# driver2.net
KiCad netlist of a schematic drawn in EAGLE
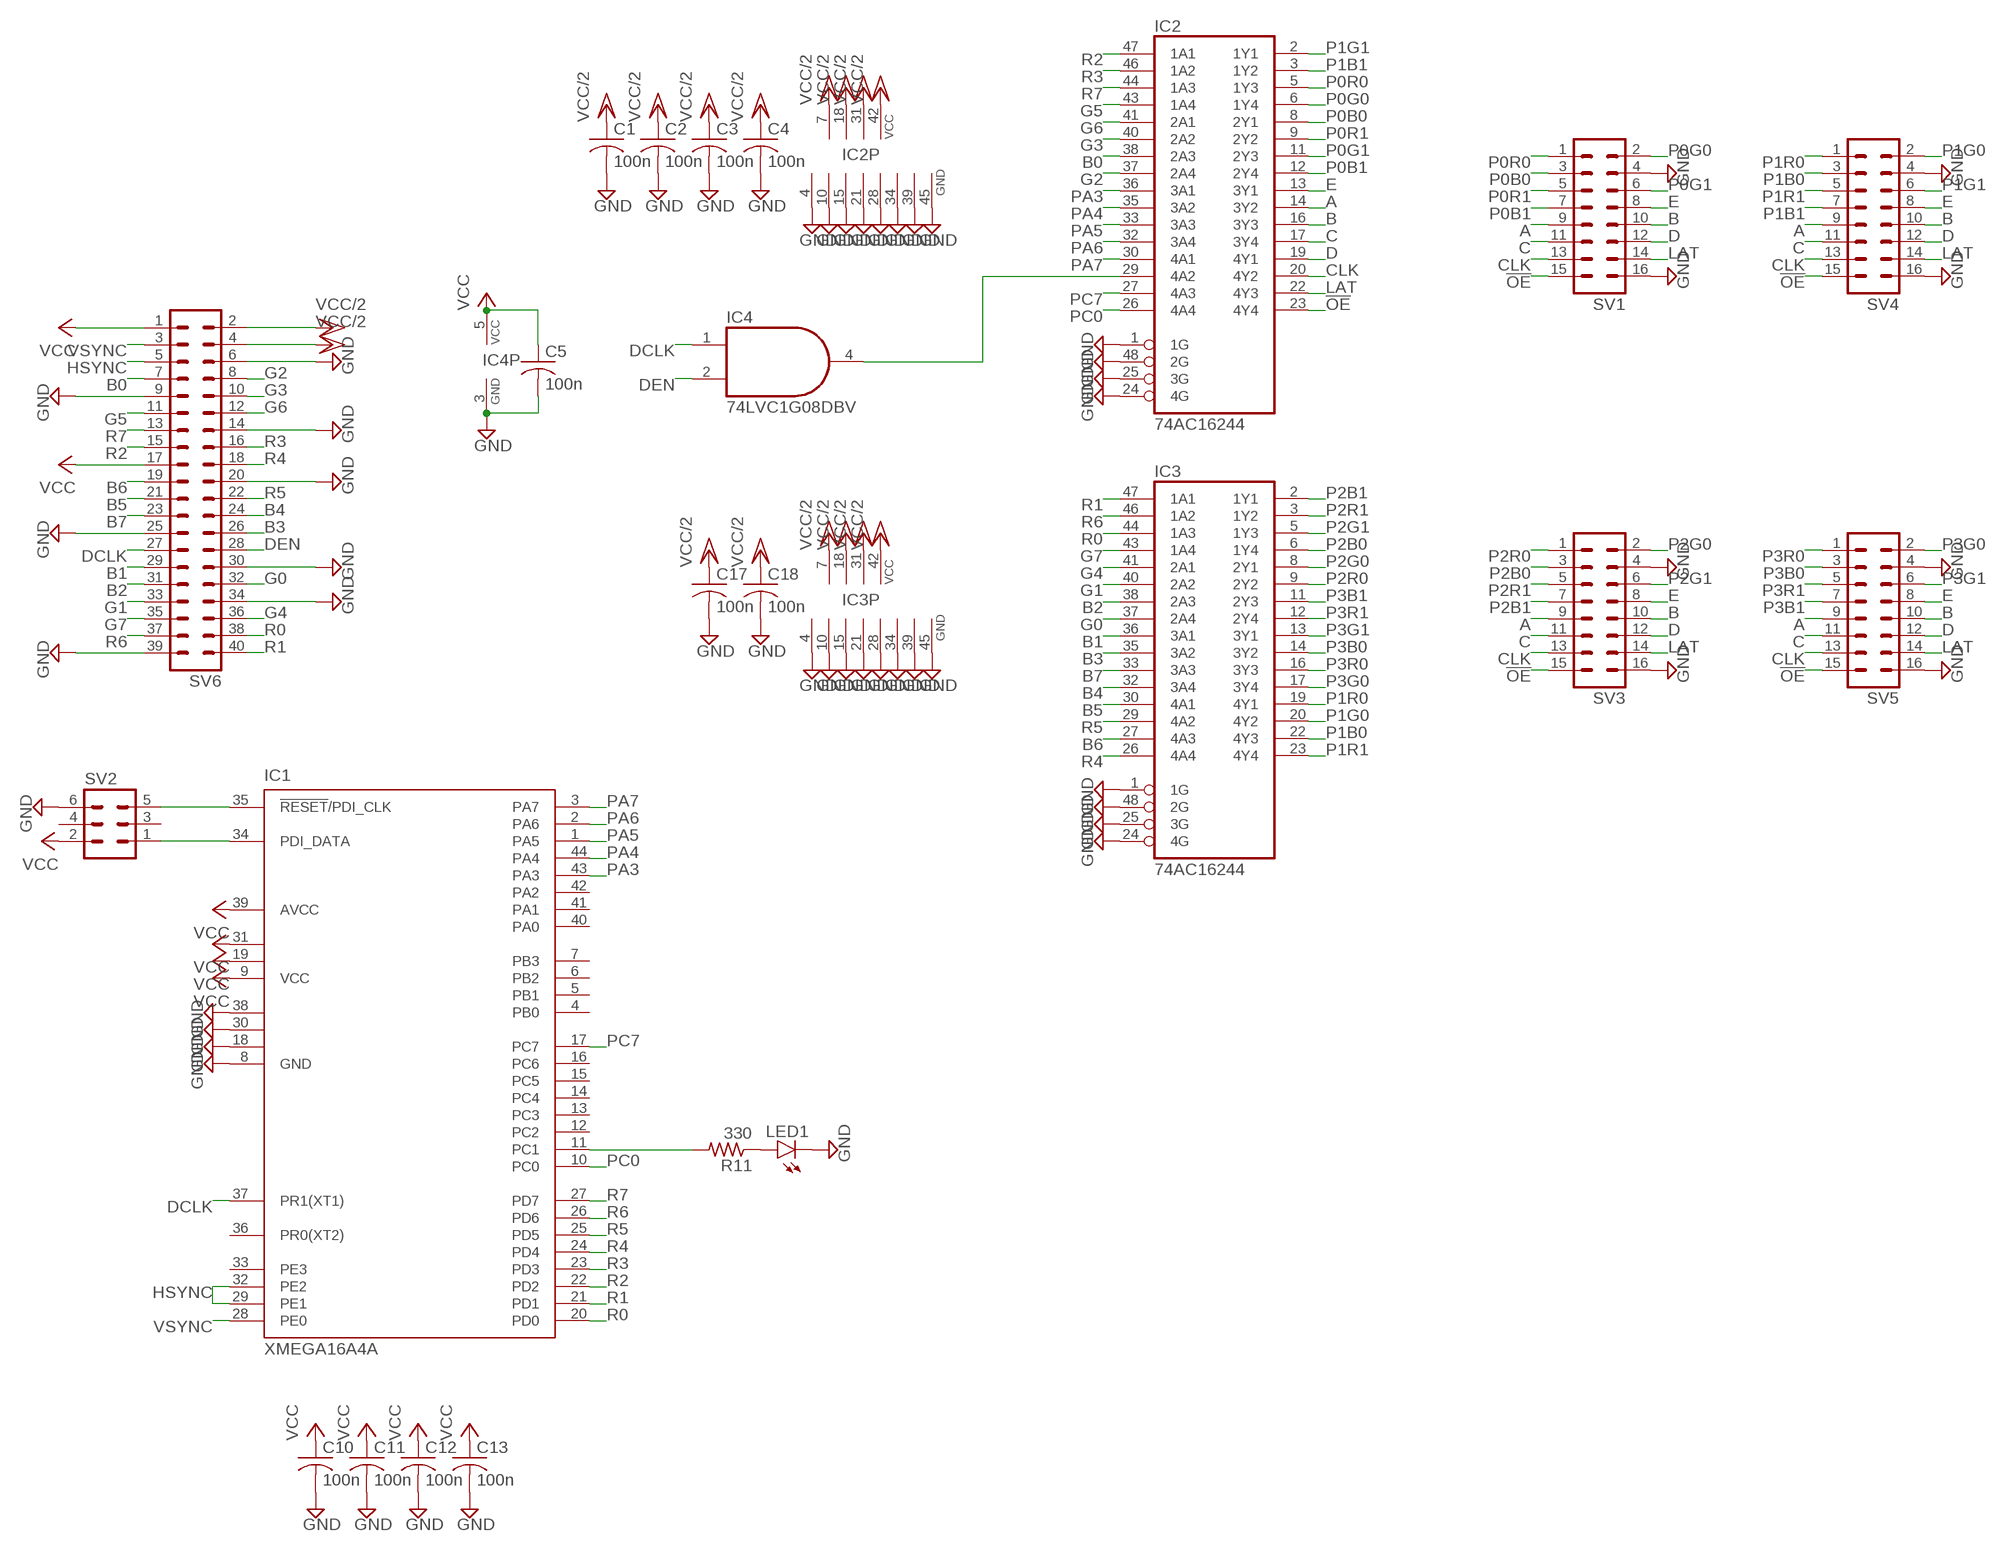
[diagram p0: schematic, sheet 1]

(export (version "E")
  (design (tool "Eeschema 10.0.6"))
  (components
    (comp (ref "C1")
      (value "100n")
      (footprint "eagle-import:C0402")
      (libsource (lib "eagle-import") (part "C-USC0402"))
    )
    (comp (ref "C2")
      (value "100n")
      (footprint "eagle-import:C0402")
      (libsource (lib "eagle-import") (part "C-USC0402"))
    )
    (comp (ref "C3")
      (value "100n")
      (footprint "eagle-import:C0402")
      (libsource (lib "eagle-import") (part "C-USC0402"))
    )
    (comp (ref "C4")
      (value "100n")
      (footprint "eagle-import:C0402")
      (libsource (lib "eagle-import") (part "C-USC0402"))
    )
    (comp (ref "C5")
      (value "100n")
      (footprint "eagle-import:C0402")
      (libsource (lib "eagle-import") (part "C-USC0402"))
    )
    (comp (ref "C10")
      (value "100n")
      (footprint "eagle-import:C0402")
      (libsource (lib "eagle-import") (part "C-USC0402"))
    )
    (comp (ref "C11")
      (value "100n")
      (footprint "eagle-import:C0402")
      (libsource (lib "eagle-import") (part "C-USC0402"))
    )
    (comp (ref "C12")
      (value "100n")
      (footprint "eagle-import:C0402")
      (libsource (lib "eagle-import") (part "C-USC0402"))
    )
    (comp (ref "C13")
      (value "100n")
      (footprint "eagle-import:C0402")
      (libsource (lib "eagle-import") (part "C-USC0402"))
    )
    (comp (ref "C17")
      (value "100n")
      (footprint "eagle-import:C0402")
      (libsource (lib "eagle-import") (part "C-USC0402"))
    )
    (comp (ref "C18")
      (value "100n")
      (footprint "eagle-import:C0402")
      (libsource (lib "eagle-import") (part "C-USC0402"))
    )
    (comp (ref "IC1")
      (value "XMEGA16A4A")
      (footprint "eagle-import:TQFP44")
      (libsource (lib "eagle-import") (part "XMEGA16A4A"))
    )
    (comp (ref "IC2")
      (value "74AC16244")
      (footprint "eagle-import:SSOP48DL")
      (libsource (lib "eagle-import") (part "74AC16244"))
    )
    (comp (ref "IC3")
      (value "74AC16244")
      (footprint "eagle-import:SSOP48DL")
      (libsource (lib "eagle-import") (part "74AC16244"))
    )
    (comp (ref "IC4")
      (value "74LVC1G08DBV")
      (footprint "eagle-import:SOT23-5")
      (libsource (lib "eagle-import") (part "741G08DBVLVC"))
    )
    (comp (ref "LED1")
      (value "LEDCHIPLED_0805")
      (footprint "eagle-import:CHIPLED_0805")
      (libsource (lib "eagle-import") (part "LEDCHIPLED_0805"))
    )
    (comp (ref "R11")
      (value "330")
      (footprint "eagle-import:R0402")
      (libsource (lib "eagle-import") (part "R-US_R0402"))
    )
    (comp (ref "SV1")
      (value "MA08-2")
      (footprint "eagle-import:MA08-2")
      (libsource (lib "eagle-import") (part "MA08-2"))
    )
    (comp (ref "SV2")
      (value "MA03-2")
      (footprint "eagle-import:MA03-2")
      (libsource (lib "eagle-import") (part "MA03-2"))
    )
    (comp (ref "SV3")
      (value "MA08-2")
      (footprint "eagle-import:MA08-2")
      (libsource (lib "eagle-import") (part "MA08-2"))
    )
    (comp (ref "SV4")
      (value "MA08-2")
      (footprint "eagle-import:MA08-2")
      (libsource (lib "eagle-import") (part "MA08-2"))
    )
    (comp (ref "SV5")
      (value "MA08-2")
      (footprint "eagle-import:MA08-2")
      (libsource (lib "eagle-import") (part "MA08-2"))
    )
    (comp (ref "SV6")
      (value "MA20-2")
      (footprint "eagle-import:MA20-2")
      (libsource (lib "eagle-import") (part "MA20-2"))
    )
  )
  (nets
    (net (code "1") (name "/A") (class "Default")
      (node (ref "IC2") (pin "14") (pinfunction "3Y2_14") (pintype "tri_state"))
      (node (ref "SV1") (pin "9") (pinfunction "9_9") (pintype "passive"))
      (node (ref "SV3") (pin "9") (pinfunction "9_9") (pintype "passive"))
      (node (ref "SV4") (pin "9") (pinfunction "9_9") (pintype "passive"))
      (node (ref "SV5") (pin "9") (pinfunction "9_9") (pintype "passive"))
    )
    (net (code "2") (name "/B") (class "Default")
      (node (ref "IC2") (pin "16") (pinfunction "3Y3_16") (pintype "tri_state"))
      (node (ref "SV1") (pin "10") (pinfunction "10_10") (pintype "passive"))
      (node (ref "SV3") (pin "10") (pinfunction "10_10") (pintype "passive"))
      (node (ref "SV4") (pin "10") (pinfunction "10_10") (pintype "passive"))
      (node (ref "SV5") (pin "10") (pinfunction "10_10") (pintype "passive"))
    )
    (net (code "3") (name "/B0") (class "Default")
      (node (ref "IC2") (pin "38") (pinfunction "2A3_38") (pintype "input"))
      (node (ref "SV6") (pin "7") (pinfunction "7_7") (pintype "passive"))
    )
    (net (code "4") (name "/B1") (class "Default")
      (node (ref "IC3") (pin "36") (pinfunction "3A1_36") (pintype "input"))
      (node (ref "SV6") (pin "29") (pinfunction "29_29") (pintype "passive"))
    )
    (net (code "5") (name "/B2") (class "Default")
      (node (ref "IC3") (pin "38") (pinfunction "2A3_38") (pintype "input"))
      (node (ref "SV6") (pin "31") (pinfunction "31_31") (pintype "passive"))
    )
    (net (code "6") (name "/B3") (class "Default")
      (node (ref "IC3") (pin "35") (pinfunction "3A2_35") (pintype "input"))
      (node (ref "SV6") (pin "26") (pinfunction "26_26") (pintype "passive"))
    )
    (net (code "7") (name "/B4") (class "Default")
      (node (ref "IC3") (pin "32") (pinfunction "3A4_32") (pintype "input"))
      (node (ref "SV6") (pin "24") (pinfunction "24_24") (pintype "passive"))
    )
    (net (code "8") (name "/B5") (class "Default")
      (node (ref "IC3") (pin "30") (pinfunction "4A1_30") (pintype "input"))
      (node (ref "SV6") (pin "21") (pinfunction "21_21") (pintype "passive"))
    )
    (net (code "9") (name "/B6") (class "Default")
      (node (ref "IC3") (pin "27") (pinfunction "4A3_27") (pintype "input"))
      (node (ref "SV6") (pin "19") (pinfunction "19_19") (pintype "passive"))
    )
    (net (code "10") (name "/B7") (class "Default")
      (node (ref "IC3") (pin "33") (pinfunction "3A3_33") (pintype "input"))
      (node (ref "SV6") (pin "23") (pinfunction "23_23") (pintype "passive"))
    )
    (net (code "11") (name "/C") (class "Default")
      (node (ref "IC2") (pin "17") (pinfunction "3Y4_17") (pintype "tri_state"))
      (node (ref "SV1") (pin "11") (pinfunction "11_11") (pintype "passive"))
      (node (ref "SV3") (pin "11") (pinfunction "11_11") (pintype "passive"))
      (node (ref "SV4") (pin "11") (pinfunction "11_11") (pintype "passive"))
      (node (ref "SV5") (pin "11") (pinfunction "11_11") (pintype "passive"))
    )
    (net (code "12") (name "/CLK") (class "Default")
      (node (ref "IC2") (pin "20") (pinfunction "4Y2_20") (pintype "tri_state"))
      (node (ref "SV1") (pin "13") (pinfunction "13_13") (pintype "passive"))
      (node (ref "SV3") (pin "13") (pinfunction "13_13") (pintype "passive"))
      (node (ref "SV4") (pin "13") (pinfunction "13_13") (pintype "passive"))
      (node (ref "SV5") (pin "13") (pinfunction "13_13") (pintype "passive"))
    )
    (net (code "13") (name "/D") (class "Default")
      (node (ref "IC2") (pin "19") (pinfunction "4Y1_19") (pintype "tri_state"))
      (node (ref "SV1") (pin "12") (pinfunction "12_12") (pintype "passive"))
      (node (ref "SV3") (pin "12") (pinfunction "12_12") (pintype "passive"))
      (node (ref "SV4") (pin "12") (pinfunction "12_12") (pintype "passive"))
      (node (ref "SV5") (pin "12") (pinfunction "12_12") (pintype "passive"))
    )
    (net (code "14") (name "/DCLK") (class "Default")
      (node (ref "IC1") (pin "37") (pinfunction "PR1(XT1)_37") (pintype "bidirectional"))
      (node (ref "IC4") (pin "1") (pinfunction "I0_1") (pintype "input"))
      (node (ref "SV6") (pin "27") (pinfunction "27_27") (pintype "passive"))
    )
    (net (code "15") (name "/DEN") (class "Default")
      (node (ref "IC4") (pin "2") (pinfunction "I1_2") (pintype "input"))
      (node (ref "SV6") (pin "28") (pinfunction "28_28") (pintype "passive"))
    )
    (net (code "16") (name "/E") (class "Default")
      (node (ref "IC2") (pin "13") (pinfunction "3Y1_13") (pintype "tri_state"))
      (node (ref "SV1") (pin "8") (pinfunction "8_8") (pintype "passive"))
      (node (ref "SV3") (pin "8") (pinfunction "8_8") (pintype "passive"))
      (node (ref "SV4") (pin "8") (pinfunction "8_8") (pintype "passive"))
      (node (ref "SV5") (pin "8") (pinfunction "8_8") (pintype "passive"))
    )
    (net (code "17") (name "/G0") (class "Default")
      (node (ref "IC3") (pin "37") (pinfunction "2A4_37") (pintype "input"))
      (node (ref "SV6") (pin "32") (pinfunction "32_32") (pintype "passive"))
    )
    (net (code "18") (name "/G1") (class "Default")
      (node (ref "IC3") (pin "40") (pinfunction "2A2_40") (pintype "input"))
      (node (ref "SV6") (pin "33") (pinfunction "33_33") (pintype "passive"))
    )
    (net (code "19") (name "/G2") (class "Default")
      (node (ref "IC2") (pin "37") (pinfunction "2A4_37") (pintype "input"))
      (node (ref "SV6") (pin "8") (pinfunction "8_8") (pintype "passive"))
    )
    (net (code "20") (name "/G3") (class "Default")
      (node (ref "IC2") (pin "40") (pinfunction "2A2_40") (pintype "input"))
      (node (ref "SV6") (pin "10") (pinfunction "10_10") (pintype "passive"))
    )
    (net (code "21") (name "/G4") (class "Default")
      (node (ref "IC3") (pin "41") (pinfunction "2A1_41") (pintype "input"))
      (node (ref "SV6") (pin "36") (pinfunction "36_36") (pintype "passive"))
    )
    (net (code "22") (name "/G5") (class "Default")
      (node (ref "IC2") (pin "43") (pinfunction "1A4_43") (pintype "input"))
      (node (ref "SV6") (pin "11") (pinfunction "11_11") (pintype "passive"))
    )
    (net (code "23") (name "/G6") (class "Default")
      (node (ref "IC2") (pin "41") (pinfunction "2A1_41") (pintype "input"))
      (node (ref "SV6") (pin "12") (pinfunction "12_12") (pintype "passive"))
    )
    (net (code "24") (name "/G7") (class "Default")
      (node (ref "IC3") (pin "43") (pinfunction "1A4_43") (pintype "input"))
      (node (ref "SV6") (pin "35") (pinfunction "35_35") (pintype "passive"))
    )
    (net (code "25") (name "/HSYNC") (class "Default")
      (node (ref "IC1") (pin "29") (pinfunction "PE1_29") (pintype "bidirectional"))
      (node (ref "IC1") (pin "32") (pinfunction "PE2_32") (pintype "bidirectional"))
      (node (ref "SV6") (pin "5") (pinfunction "5_5") (pintype "passive"))
    )
    (net (code "26") (name "/LAT") (class "Default")
      (node (ref "IC2") (pin "22") (pinfunction "4Y3_22") (pintype "tri_state"))
      (node (ref "SV1") (pin "14") (pinfunction "14_14") (pintype "passive"))
      (node (ref "SV3") (pin "14") (pinfunction "14_14") (pintype "passive"))
      (node (ref "SV4") (pin "14") (pinfunction "14_14") (pintype "passive"))
      (node (ref "SV5") (pin "14") (pinfunction "14_14") (pintype "passive"))
    )
    (net (code "27") (name "/P0B0") (class "Default")
      (node (ref "IC2") (pin "8") (pinfunction "2Y1_8") (pintype "tri_state"))
      (node (ref "SV1") (pin "3") (pinfunction "3_3") (pintype "passive"))
    )
    (net (code "28") (name "/P0B1") (class "Default")
      (node (ref "IC2") (pin "12") (pinfunction "2Y4_12") (pintype "tri_state"))
      (node (ref "SV1") (pin "7") (pinfunction "7_7") (pintype "passive"))
    )
    (net (code "29") (name "/P0G0") (class "Default")
      (node (ref "IC2") (pin "6") (pinfunction "1Y4_6") (pintype "tri_state"))
      (node (ref "SV1") (pin "2") (pinfunction "2_2") (pintype "passive"))
    )
    (net (code "30") (name "/P0G1") (class "Default")
      (node (ref "IC2") (pin "11") (pinfunction "2Y3_11") (pintype "tri_state"))
      (node (ref "SV1") (pin "6") (pinfunction "6_6") (pintype "passive"))
    )
    (net (code "31") (name "/P0R0") (class "Default")
      (node (ref "IC2") (pin "5") (pinfunction "1Y3_5") (pintype "tri_state"))
      (node (ref "SV1") (pin "1") (pinfunction "1_1") (pintype "passive"))
    )
    (net (code "32") (name "/P0R1") (class "Default")
      (node (ref "IC2") (pin "9") (pinfunction "2Y2_9") (pintype "tri_state"))
      (node (ref "SV1") (pin "5") (pinfunction "5_5") (pintype "passive"))
    )
    (net (code "33") (name "/P1B0") (class "Default")
      (node (ref "IC3") (pin "22") (pinfunction "4Y3_22") (pintype "tri_state"))
      (node (ref "SV4") (pin "3") (pinfunction "3_3") (pintype "passive"))
    )
    (net (code "34") (name "/P1B1") (class "Default")
      (node (ref "IC2") (pin "3") (pinfunction "1Y2_3") (pintype "tri_state"))
      (node (ref "SV4") (pin "7") (pinfunction "7_7") (pintype "passive"))
    )
    (net (code "35") (name "/P1G0") (class "Default")
      (node (ref "IC3") (pin "20") (pinfunction "4Y2_20") (pintype "tri_state"))
      (node (ref "SV4") (pin "2") (pinfunction "2_2") (pintype "passive"))
    )
    (net (code "36") (name "/P1G1") (class "Default")
      (node (ref "IC2") (pin "2") (pinfunction "1Y1_2") (pintype "tri_state"))
      (node (ref "SV4") (pin "6") (pinfunction "6_6") (pintype "passive"))
    )
    (net (code "37") (name "/P1R0") (class "Default")
      (node (ref "IC3") (pin "19") (pinfunction "4Y1_19") (pintype "tri_state"))
      (node (ref "SV4") (pin "1") (pinfunction "1_1") (pintype "passive"))
    )
    (net (code "38") (name "/P1R1") (class "Default")
      (node (ref "IC3") (pin "23") (pinfunction "4Y4_23") (pintype "tri_state"))
      (node (ref "SV4") (pin "5") (pinfunction "5_5") (pintype "passive"))
    )
    (net (code "39") (name "/P2B0") (class "Default")
      (node (ref "IC3") (pin "6") (pinfunction "1Y4_6") (pintype "tri_state"))
      (node (ref "SV3") (pin "3") (pinfunction "3_3") (pintype "passive"))
    )
    (net (code "40") (name "/P2B1") (class "Default")
      (node (ref "IC3") (pin "2") (pinfunction "1Y1_2") (pintype "tri_state"))
      (node (ref "SV3") (pin "7") (pinfunction "7_7") (pintype "passive"))
    )
    (net (code "41") (name "/P2G0") (class "Default")
      (node (ref "IC3") (pin "8") (pinfunction "2Y1_8") (pintype "tri_state"))
      (node (ref "SV3") (pin "2") (pinfunction "2_2") (pintype "passive"))
    )
    (net (code "42") (name "/P2G1") (class "Default")
      (node (ref "IC3") (pin "5") (pinfunction "1Y3_5") (pintype "tri_state"))
      (node (ref "SV3") (pin "6") (pinfunction "6_6") (pintype "passive"))
    )
    (net (code "43") (name "/P2R0") (class "Default")
      (node (ref "IC3") (pin "9") (pinfunction "2Y2_9") (pintype "tri_state"))
      (node (ref "SV3") (pin "1") (pinfunction "1_1") (pintype "passive"))
    )
    (net (code "44") (name "/P2R1") (class "Default")
      (node (ref "IC3") (pin "3") (pinfunction "1Y2_3") (pintype "tri_state"))
      (node (ref "SV3") (pin "5") (pinfunction "5_5") (pintype "passive"))
    )
    (net (code "45") (name "/P3B0") (class "Default")
      (node (ref "IC3") (pin "14") (pinfunction "3Y2_14") (pintype "tri_state"))
      (node (ref "SV5") (pin "3") (pinfunction "3_3") (pintype "passive"))
    )
    (net (code "46") (name "/P3B1") (class "Default")
      (node (ref "IC3") (pin "11") (pinfunction "2Y3_11") (pintype "tri_state"))
      (node (ref "SV5") (pin "7") (pinfunction "7_7") (pintype "passive"))
    )
    (net (code "47") (name "/P3G0") (class "Default")
      (node (ref "IC3") (pin "17") (pinfunction "3Y4_17") (pintype "tri_state"))
      (node (ref "SV5") (pin "2") (pinfunction "2_2") (pintype "passive"))
    )
    (net (code "48") (name "/P3G1") (class "Default")
      (node (ref "IC3") (pin "13") (pinfunction "3Y1_13") (pintype "tri_state"))
      (node (ref "SV5") (pin "6") (pinfunction "6_6") (pintype "passive"))
    )
    (net (code "49") (name "/P3R0") (class "Default")
      (node (ref "IC3") (pin "16") (pinfunction "3Y3_16") (pintype "tri_state"))
      (node (ref "SV5") (pin "1") (pinfunction "1_1") (pintype "passive"))
    )
    (net (code "50") (name "/P3R1") (class "Default")
      (node (ref "IC3") (pin "12") (pinfunction "2Y4_12") (pintype "tri_state"))
      (node (ref "SV5") (pin "5") (pinfunction "5_5") (pintype "passive"))
    )
    (net (code "51") (name "/PA3") (class "Default")
      (node (ref "IC1") (pin "43") (pinfunction "PA3_43") (pintype "bidirectional"))
      (node (ref "IC2") (pin "36") (pinfunction "3A1_36") (pintype "input"))
    )
    (net (code "52") (name "/PA4") (class "Default")
      (node (ref "IC1") (pin "44") (pinfunction "PA4_44") (pintype "bidirectional"))
      (node (ref "IC2") (pin "35") (pinfunction "3A2_35") (pintype "input"))
    )
    (net (code "53") (name "/PA5") (class "Default")
      (node (ref "IC1") (pin "1") (pinfunction "PA5_1") (pintype "bidirectional"))
      (node (ref "IC2") (pin "33") (pinfunction "3A3_33") (pintype "input"))
    )
    (net (code "54") (name "/PA6") (class "Default")
      (node (ref "IC1") (pin "2") (pinfunction "PA6_2") (pintype "bidirectional"))
      (node (ref "IC2") (pin "32") (pinfunction "3A4_32") (pintype "input"))
    )
    (net (code "55") (name "/PA7") (class "Default")
      (node (ref "IC1") (pin "3") (pinfunction "PA7_3") (pintype "bidirectional"))
      (node (ref "IC2") (pin "30") (pinfunction "4A1_30") (pintype "input"))
    )
    (net (code "56") (name "/PC0") (class "Default")
      (node (ref "IC1") (pin "10") (pinfunction "PC0_10") (pintype "bidirectional"))
      (node (ref "IC2") (pin "26") (pinfunction "4A4_26") (pintype "input"))
    )
    (net (code "57") (name "/PC7") (class "Default")
      (node (ref "IC1") (pin "17") (pinfunction "PC7_17") (pintype "bidirectional"))
      (node (ref "IC2") (pin "27") (pinfunction "4A3_27") (pintype "input"))
    )
    (net (code "58") (name "/R0") (class "Default")
      (node (ref "IC1") (pin "20") (pinfunction "PD0_20") (pintype "bidirectional"))
      (node (ref "IC3") (pin "44") (pinfunction "1A3_44") (pintype "input"))
      (node (ref "SV6") (pin "38") (pinfunction "38_38") (pintype "passive"))
    )
    (net (code "59") (name "/R1") (class "Default")
      (node (ref "IC1") (pin "21") (pinfunction "PD1_21") (pintype "bidirectional"))
      (node (ref "IC3") (pin "47") (pinfunction "1A1_47") (pintype "input"))
      (node (ref "SV6") (pin "40") (pinfunction "40_40") (pintype "passive"))
    )
    (net (code "60") (name "/R2") (class "Default")
      (node (ref "IC1") (pin "22") (pinfunction "PD2_22") (pintype "bidirectional"))
      (node (ref "IC2") (pin "47") (pinfunction "1A1_47") (pintype "input"))
      (node (ref "SV6") (pin "15") (pinfunction "15_15") (pintype "passive"))
    )
    (net (code "61") (name "/R3") (class "Default")
      (node (ref "IC1") (pin "23") (pinfunction "PD3_23") (pintype "bidirectional"))
      (node (ref "IC2") (pin "46") (pinfunction "1A2_46") (pintype "input"))
      (node (ref "SV6") (pin "16") (pinfunction "16_16") (pintype "passive"))
    )
    (net (code "62") (name "/R4") (class "Default")
      (node (ref "IC1") (pin "24") (pinfunction "PD4_24") (pintype "bidirectional"))
      (node (ref "IC3") (pin "26") (pinfunction "4A4_26") (pintype "input"))
      (node (ref "SV6") (pin "18") (pinfunction "18_18") (pintype "passive"))
    )
    (net (code "63") (name "/R5") (class "Default")
      (node (ref "IC1") (pin "25") (pinfunction "PD5_25") (pintype "bidirectional"))
      (node (ref "IC3") (pin "29") (pinfunction "4A2_29") (pintype "input"))
      (node (ref "SV6") (pin "22") (pinfunction "22_22") (pintype "passive"))
    )
    (net (code "64") (name "/R6") (class "Default")
      (node (ref "IC1") (pin "26") (pinfunction "PD6_26") (pintype "bidirectional"))
      (node (ref "IC3") (pin "46") (pinfunction "1A2_46") (pintype "input"))
      (node (ref "SV6") (pin "37") (pinfunction "37_37") (pintype "passive"))
    )
    (net (code "65") (name "/R7") (class "Default")
      (node (ref "IC1") (pin "27") (pinfunction "PD7_27") (pintype "bidirectional"))
      (node (ref "IC2") (pin "44") (pinfunction "1A3_44") (pintype "input"))
      (node (ref "SV6") (pin "13") (pinfunction "13_13") (pintype "passive"))
    )
    (net (code "66") (name "/VSYNC") (class "Default")
      (node (ref "IC1") (pin "28") (pinfunction "PE0_28") (pintype "bidirectional"))
      (node (ref "SV6") (pin "3") (pinfunction "3_3") (pintype "passive"))
    )
    (net (code "67") (name "/~{OE}") (class "Default")
      (node (ref "IC2") (pin "23") (pinfunction "4Y4_23") (pintype "tri_state"))
      (node (ref "SV1") (pin "15") (pinfunction "15_15") (pintype "passive"))
      (node (ref "SV3") (pin "15") (pinfunction "15_15") (pintype "passive"))
      (node (ref "SV4") (pin "15") (pinfunction "15_15") (pintype "passive"))
      (node (ref "SV5") (pin "15") (pinfunction "15_15") (pintype "passive"))
    )
    (net (code "68") (name "GND") (class "Default")
      (node (ref "C1") (pin "2") (pinfunction "2_2") (pintype "passive"))
      (node (ref "C10") (pin "2") (pinfunction "2_2") (pintype "passive"))
      (node (ref "C11") (pin "2") (pinfunction "2_2") (pintype "passive"))
      (node (ref "C12") (pin "2") (pinfunction "2_2") (pintype "passive"))
      (node (ref "C13") (pin "2") (pinfunction "2_2") (pintype "passive"))
      (node (ref "C17") (pin "2") (pinfunction "2_2") (pintype "passive"))
      (node (ref "C18") (pin "2") (pinfunction "2_2") (pintype "passive"))
      (node (ref "C2") (pin "2") (pinfunction "2_2") (pintype "passive"))
      (node (ref "C3") (pin "2") (pinfunction "2_2") (pintype "passive"))
      (node (ref "C4") (pin "2") (pinfunction "2_2") (pintype "passive"))
      (node (ref "C5") (pin "2") (pinfunction "2_2") (pintype "passive"))
      (node (ref "IC1") (pin "18") (pinfunction "GND1_18") (pintype "power_in"))
      (node (ref "IC1") (pin "30") (pinfunction "GND2_30") (pintype "power_in"))
      (node (ref "IC1") (pin "38") (pinfunction "GND3_38") (pintype "power_in"))
      (node (ref "IC1") (pin "8") (pinfunction "GND_8") (pintype "power_in"))
      (node (ref "IC2") (pin "1") (pinfunction "1G_1") (pintype "input"))
      (node (ref "IC2") (pin "10") (pinfunction "GND_10") (pintype "power_in"))
      (node (ref "IC2") (pin "15") (pinfunction "GND_15") (pintype "power_in"))
      (node (ref "IC2") (pin "21") (pinfunction "GND_21") (pintype "power_in"))
      (node (ref "IC2") (pin "24") (pinfunction "4G_24") (pintype "input"))
      (node (ref "IC2") (pin "25") (pinfunction "3G_25") (pintype "input"))
      (node (ref "IC2") (pin "28") (pinfunction "GND_28") (pintype "power_in"))
      (node (ref "IC2") (pin "34") (pinfunction "GND_34") (pintype "power_in"))
      (node (ref "IC2") (pin "39") (pinfunction "GND_39") (pintype "power_in"))
      (node (ref "IC2") (pin "4") (pinfunction "GND_4") (pintype "power_in"))
      (node (ref "IC2") (pin "45") (pinfunction "GND_45") (pintype "power_in"))
      (node (ref "IC2") (pin "48") (pinfunction "2G_48") (pintype "input"))
      (node (ref "IC3") (pin "1") (pinfunction "1G_1") (pintype "input"))
      (node (ref "IC3") (pin "10") (pinfunction "GND_10") (pintype "power_in"))
      (node (ref "IC3") (pin "15") (pinfunction "GND_15") (pintype "power_in"))
      (node (ref "IC3") (pin "21") (pinfunction "GND_21") (pintype "power_in"))
      (node (ref "IC3") (pin "24") (pinfunction "4G_24") (pintype "input"))
      (node (ref "IC3") (pin "25") (pinfunction "3G_25") (pintype "input"))
      (node (ref "IC3") (pin "28") (pinfunction "GND_28") (pintype "power_in"))
      (node (ref "IC3") (pin "34") (pinfunction "GND_34") (pintype "power_in"))
      (node (ref "IC3") (pin "39") (pinfunction "GND_39") (pintype "power_in"))
      (node (ref "IC3") (pin "4") (pinfunction "GND_4") (pintype "power_in"))
      (node (ref "IC3") (pin "45") (pinfunction "GND_45") (pintype "power_in"))
      (node (ref "IC3") (pin "48") (pinfunction "2G_48") (pintype "input"))
      (node (ref "IC4") (pin "3") (pinfunction "GND_3") (pintype "power_in"))
      (node (ref "LED1") (pin "C") (pinfunction "C_C") (pintype "passive"))
      (node (ref "SV1") (pin "16") (pinfunction "16_16") (pintype "passive"))
      (node (ref "SV1") (pin "4") (pinfunction "4_4") (pintype "passive"))
      (node (ref "SV2") (pin "6") (pinfunction "6_6") (pintype "passive"))
      (node (ref "SV3") (pin "16") (pinfunction "16_16") (pintype "passive"))
      (node (ref "SV3") (pin "4") (pinfunction "4_4") (pintype "passive"))
      (node (ref "SV4") (pin "16") (pinfunction "16_16") (pintype "passive"))
      (node (ref "SV4") (pin "4") (pinfunction "4_4") (pintype "passive"))
      (node (ref "SV5") (pin "16") (pinfunction "16_16") (pintype "passive"))
      (node (ref "SV5") (pin "4") (pinfunction "4_4") (pintype "passive"))
      (node (ref "SV6") (pin "14") (pinfunction "14_14") (pintype "passive"))
      (node (ref "SV6") (pin "20") (pinfunction "20_20") (pintype "passive"))
      (node (ref "SV6") (pin "25") (pinfunction "25_25") (pintype "passive"))
      (node (ref "SV6") (pin "30") (pinfunction "30_30") (pintype "passive"))
      (node (ref "SV6") (pin "34") (pinfunction "34_34") (pintype "passive"))
      (node (ref "SV6") (pin "39") (pinfunction "39_39") (pintype "passive"))
      (node (ref "SV6") (pin "6") (pinfunction "6_6") (pintype "passive"))
      (node (ref "SV6") (pin "9") (pinfunction "9_9") (pintype "passive"))
    )
    (net (code "69") (name "Net-(IC1-PC1)") (class "Default")
      (node (ref "IC1") (pin "11") (pinfunction "PC1_11") (pintype "bidirectional"))
      (node (ref "R11") (pin "2") (pinfunction "2_2") (pintype "passive"))
    )
    (net (code "70") (name "Net-(IC1-PDI_DATA)") (class "Default")
      (node (ref "IC1") (pin "34") (pinfunction "PDI_DATA_34") (pintype "bidirectional"))
      (node (ref "SV2") (pin "1") (pinfunction "1_1") (pintype "passive"))
    )
    (net (code "71") (name "Net-(IC1-~{RESET}{slash}PDI_CLK)") (class "Default")
      (node (ref "IC1") (pin "35") (pinfunction "~{RESET}/PDI_CLK_35") (pintype "bidirectional"))
      (node (ref "SV2") (pin "5") (pinfunction "5_5") (pintype "passive"))
    )
    (net (code "72") (name "Net-(IC2A-4A2)") (class "Default")
      (node (ref "IC2") (pin "29") (pinfunction "4A2_29") (pintype "input"))
      (node (ref "IC4") (pin "4") (pinfunction "O_4") (pintype "output"))
    )
    (net (code "73") (name "Net-(LED1-PadA)") (class "Default")
      (node (ref "LED1") (pin "A") (pinfunction "A_A") (pintype "passive"))
      (node (ref "R11") (pin "1") (pinfunction "1_1") (pintype "passive"))
    )
    (net (code "74") (name "VCC") (class "Default")
      (node (ref "C10") (pin "1") (pinfunction "1_1") (pintype "passive"))
      (node (ref "C11") (pin "1") (pinfunction "1_1") (pintype "passive"))
      (node (ref "C12") (pin "1") (pinfunction "1_1") (pintype "passive"))
      (node (ref "C13") (pin "1") (pinfunction "1_1") (pintype "passive"))
      (node (ref "C5") (pin "1") (pinfunction "1_1") (pintype "passive"))
      (node (ref "IC1") (pin "19") (pinfunction "VCC1_19") (pintype "power_in"))
      (node (ref "IC1") (pin "31") (pinfunction "VCC2_31") (pintype "power_in"))
      (node (ref "IC1") (pin "39") (pinfunction "AVCC_39") (pintype "power_in"))
      (node (ref "IC1") (pin "9") (pinfunction "VCC_9") (pintype "power_in"))
      (node (ref "IC4") (pin "5") (pinfunction "VCC_5") (pintype "power_in"))
      (node (ref "SV2") (pin "2") (pinfunction "2_2") (pintype "passive"))
      (node (ref "SV6") (pin "1") (pinfunction "1_1") (pintype "passive"))
      (node (ref "SV6") (pin "17") (pinfunction "17_17") (pintype "passive"))
    )
    (net (code "75") (name "VCC{slash}2") (class "Default")
      (node (ref "C1") (pin "1") (pinfunction "1_1") (pintype "passive"))
      (node (ref "C17") (pin "1") (pinfunction "1_1") (pintype "passive"))
      (node (ref "C18") (pin "1") (pinfunction "1_1") (pintype "passive"))
      (node (ref "C2") (pin "1") (pinfunction "1_1") (pintype "passive"))
      (node (ref "C3") (pin "1") (pinfunction "1_1") (pintype "passive"))
      (node (ref "C4") (pin "1") (pinfunction "1_1") (pintype "passive"))
      (node (ref "IC2") (pin "18") (pinfunction "VCC_18") (pintype "power_in"))
      (node (ref "IC2") (pin "31") (pinfunction "VCC_31") (pintype "power_in"))
      (node (ref "IC2") (pin "42") (pinfunction "VCC_42") (pintype "power_in"))
      (node (ref "IC2") (pin "7") (pinfunction "VCC_7") (pintype "power_in"))
      (node (ref "IC3") (pin "18") (pinfunction "VCC_18") (pintype "power_in"))
      (node (ref "IC3") (pin "31") (pinfunction "VCC_31") (pintype "power_in"))
      (node (ref "IC3") (pin "42") (pinfunction "VCC_42") (pintype "power_in"))
      (node (ref "IC3") (pin "7") (pinfunction "VCC_7") (pintype "power_in"))
      (node (ref "SV6") (pin "2") (pinfunction "2_2") (pintype "passive"))
      (node (ref "SV6") (pin "4") (pinfunction "4_4") (pintype "passive"))
    )
    (net (code "76") (name "unconnected-(IC1-PA0-Pad40)") (class "Default")
      (node (ref "IC1") (pin "40") (pinfunction "PA0_40") (pintype "bidirectional"))
    )
    (net (code "77") (name "unconnected-(IC1-PA1-Pad41)") (class "Default")
      (node (ref "IC1") (pin "41") (pinfunction "PA1_41") (pintype "bidirectional"))
    )
    (net (code "78") (name "unconnected-(IC1-PA2-Pad42)") (class "Default")
      (node (ref "IC1") (pin "42") (pinfunction "PA2_42") (pintype "bidirectional"))
    )
    (net (code "79") (name "unconnected-(IC1-PB0-Pad4)") (class "Default")
      (node (ref "IC1") (pin "4") (pinfunction "PB0_4") (pintype "bidirectional"))
    )
    (net (code "80") (name "unconnected-(IC1-PB1-Pad5)") (class "Default")
      (node (ref "IC1") (pin "5") (pinfunction "PB1_5") (pintype "bidirectional"))
    )
    (net (code "81") (name "unconnected-(IC1-PB2-Pad6)") (class "Default")
      (node (ref "IC1") (pin "6") (pinfunction "PB2_6") (pintype "bidirectional"))
    )
    (net (code "82") (name "unconnected-(IC1-PB3-Pad7)") (class "Default")
      (node (ref "IC1") (pin "7") (pinfunction "PB3_7") (pintype "bidirectional"))
    )
    (net (code "83") (name "unconnected-(IC1-PC2-Pad12)") (class "Default")
      (node (ref "IC1") (pin "12") (pinfunction "PC2_12") (pintype "bidirectional"))
    )
    (net (code "84") (name "unconnected-(IC1-PC3-Pad13)") (class "Default")
      (node (ref "IC1") (pin "13") (pinfunction "PC3_13") (pintype "bidirectional"))
    )
    (net (code "85") (name "unconnected-(IC1-PC4-Pad14)") (class "Default")
      (node (ref "IC1") (pin "14") (pinfunction "PC4_14") (pintype "bidirectional"))
    )
    (net (code "86") (name "unconnected-(IC1-PC5-Pad15)") (class "Default")
      (node (ref "IC1") (pin "15") (pinfunction "PC5_15") (pintype "bidirectional"))
    )
    (net (code "87") (name "unconnected-(IC1-PC6-Pad16)") (class "Default")
      (node (ref "IC1") (pin "16") (pinfunction "PC6_16") (pintype "bidirectional"))
    )
    (net (code "88") (name "unconnected-(IC1-PE3-Pad33)") (class "Default")
      (node (ref "IC1") (pin "33") (pinfunction "PE3_33") (pintype "bidirectional"))
    )
    (net (code "89") (name "unconnected-(IC1-PR0(XT2)-Pad36)") (class "Default")
      (node (ref "IC1") (pin "36") (pinfunction "PR0(XT2)_36") (pintype "bidirectional"))
    )
    (net (code "90") (name "unconnected-(SV2-Pad3)") (class "Default")
      (node (ref "SV2") (pin "3") (pinfunction "3_3") (pintype "passive"))
    )
    (net (code "91") (name "unconnected-(SV2-Pad4)") (class "Default")
      (node (ref "SV2") (pin "4") (pinfunction "4_4") (pintype "passive"))
    )
  )
)
